# eBox_ACdetect2.net
KiCad netlist of a schematic drawn in Altium Designer
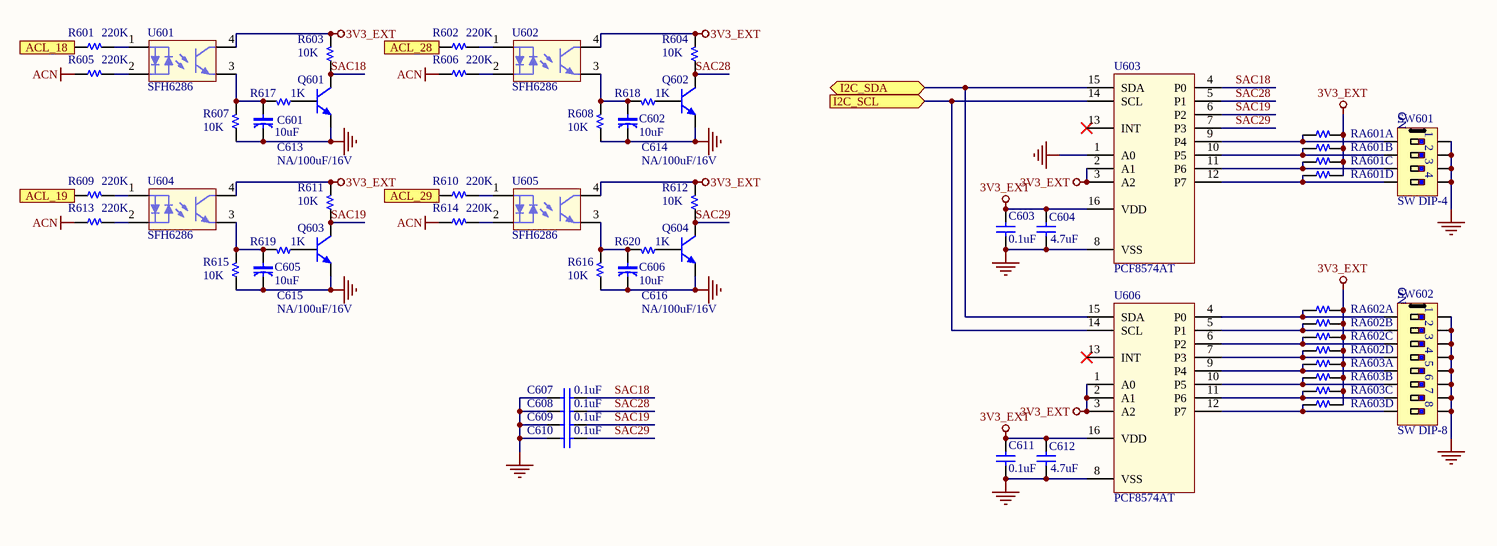
[diagram p0: eBox_ACdetect2.SchDoc]

(export (version "E")
  (design (tool "Eeschema 10.0.6"))
  (components
    (comp (ref "C601")
      (value "10uF")
      (footprint "C 0805")
      (description "CAP CER 0.1UF 50V X7R 0805")
      (libsource (lib "chipfc_altium_libs") (part "Capacitor NP"))
    )
    (comp (ref "C602")
      (value "10uF")
      (footprint "C 0805")
      (description "CAP CER 0.1UF 50V X7R 0805")
      (libsource (lib "chipfc_altium_libs") (part "Capacitor NP"))
    )
    (comp (ref "C603")
      (value "0.1uF")
      (footprint "C 0603")
      (description "CAP CER 0.1UF 50V X7R 0603")
      (libsource (lib "chipfc_altium_libs") (part "Capacitor NP"))
    )
    (comp (ref "C604")
      (value "4.7uF")
      (footprint "C 0603")
      (description "CAP CER 4.7UF 50V X7R 0603")
      (libsource (lib "chipfc_altium_libs") (part "Capacitor NP"))
    )
    (comp (ref "C605")
      (value "10uF")
      (footprint "C 0805")
      (description "CAP CER 0.1UF 50V X7R 0805")
      (libsource (lib "chipfc_altium_libs") (part "Capacitor NP"))
    )
    (comp (ref "C606")
      (value "10uF")
      (footprint "C 0805")
      (description "CAP CER 0.1UF 50V X7R 0805")
      (libsource (lib "chipfc_altium_libs") (part "Capacitor NP"))
    )
    (comp (ref "C607")
      (value "0.1uF")
      (footprint "C 0805")
      (description "CAP CER 0.1UF 50V X7R 0805")
      (libsource (lib "chipfc_altium_libs") (part "Capacitor NP"))
    )
    (comp (ref "C608")
      (value "0.1uF")
      (footprint "C 0805")
      (description "CAP CER 0.1UF 50V X7R 0805")
      (libsource (lib "chipfc_altium_libs") (part "Capacitor NP"))
    )
    (comp (ref "C609")
      (value "0.1uF")
      (footprint "C 0805")
      (description "CAP CER 0.1UF 50V X7R 0805")
      (libsource (lib "chipfc_altium_libs") (part "Capacitor NP"))
    )
    (comp (ref "C610")
      (value "0.1uF")
      (footprint "C 0805")
      (description "CAP CER 0.1UF 50V X7R 0805")
      (libsource (lib "chipfc_altium_libs") (part "Capacitor NP"))
    )
    (comp (ref "C611")
      (value "0.1uF")
      (footprint "C 0603")
      (description "CAP CER 0.1UF 50V X7R 0603")
      (libsource (lib "chipfc_altium_libs") (part "Capacitor NP"))
    )
    (comp (ref "C612")
      (value "4.7uF")
      (footprint "C 0603")
      (description "CAP CER 4.7UF 50V X7R 0603")
      (libsource (lib "chipfc_altium_libs") (part "Capacitor NP"))
    )
    (comp (ref "C613")
      (value "NA/100uF/16V")
      (footprint "CYL/D.200/LS.75")
      (description "CAP ALUM 100UF 20% 16V RADIAL")
      (libsource (lib "chipfc_altium_libs") (part "Capacitor"))
    )
    (comp (ref "C614")
      (value "NA/100uF/16V")
      (footprint "CYL/D.200/LS.75")
      (description "CAP ALUM 100UF 20% 16V RADIAL")
      (libsource (lib "chipfc_altium_libs") (part "Capacitor"))
    )
    (comp (ref "C615")
      (value "NA/100uF/16V")
      (footprint "CYL/D.200/LS.75")
      (description "CAP ALUM 100UF 20% 16V RADIAL")
      (libsource (lib "chipfc_altium_libs") (part "Capacitor"))
    )
    (comp (ref "C616")
      (value "NA/100uF/16V")
      (footprint "CYL/D.200/LS.75")
      (description "CAP ALUM 100UF 20% 16V RADIAL")
      (libsource (lib "chipfc_altium_libs") (part "Capacitor"))
    )
    (comp (ref "Q601")
      (value "MMBT3904LT1G")
      (footprint "SOT-23")
      (description "TRANS NPN 40V 0.2A SOT23")
      (libsource (lib "chipfc_altium_libs") (part "Transistor NPN"))
    )
    (comp (ref "Q602")
      (value "MMBT3904LT1G")
      (footprint "SOT-23")
      (description "TRANS NPN 40V 0.2A SOT23")
      (libsource (lib "chipfc_altium_libs") (part "Transistor NPN"))
    )
    (comp (ref "Q603")
      (value "MMBT3904LT1G")
      (footprint "SOT-23")
      (description "TRANS NPN 40V 0.2A SOT23")
      (libsource (lib "chipfc_altium_libs") (part "Transistor NPN"))
    )
    (comp (ref "Q604")
      (value "MMBT3904LT1G")
      (footprint "SOT-23")
      (description "TRANS NPN 40V 0.2A SOT23")
      (libsource (lib "chipfc_altium_libs") (part "Transistor NPN"))
    )
    (comp (ref "R601")
      (value "220K")
      (footprint "R 0805")
      (description "RES SMD 220K OHM 1% 1/8W 0805")
      (libsource (lib "chipfc_altium_libs") (part "Resistor"))
    )
    (comp (ref "R602")
      (value "220K")
      (footprint "R 0805")
      (description "RES SMD 220K OHM 1% 1/8W 0805")
      (libsource (lib "chipfc_altium_libs") (part "Resistor"))
    )
    (comp (ref "R603")
      (value "10K")
      (footprint "R 0805")
      (description "RES SMD 10K OHM 1% 1/8W 0805")
      (libsource (lib "chipfc_altium_libs") (part "Resistor"))
    )
    (comp (ref "R604")
      (value "10K")
      (footprint "R 0805")
      (description "RES SMD 10K OHM 1% 1/8W 0805")
      (libsource (lib "chipfc_altium_libs") (part "Resistor"))
    )
    (comp (ref "R605")
      (value "220K")
      (footprint "R 0805")
      (description "RES SMD 220K OHM 1% 1/8W 0805")
      (libsource (lib "chipfc_altium_libs") (part "Resistor"))
    )
    (comp (ref "R606")
      (value "220K")
      (footprint "R 0805")
      (description "RES SMD 220K OHM 1% 1/8W 0805")
      (libsource (lib "chipfc_altium_libs") (part "Resistor"))
    )
    (comp (ref "R607")
      (value "10K")
      (footprint "R 0805")
      (description "RES SMD 10K OHM 1% 1/8W 0805")
      (libsource (lib "chipfc_altium_libs") (part "Resistor"))
    )
    (comp (ref "R608")
      (value "10K")
      (footprint "R 0805")
      (description "RES SMD 10K OHM 1% 1/8W 0805")
      (libsource (lib "chipfc_altium_libs") (part "Resistor"))
    )
    (comp (ref "R609")
      (value "220K")
      (footprint "R 0805")
      (description "RES SMD 220K OHM 1% 1/8W 0805")
      (libsource (lib "chipfc_altium_libs") (part "Resistor"))
    )
    (comp (ref "R610")
      (value "220K")
      (footprint "R 0805")
      (description "RES SMD 220K OHM 1% 1/8W 0805")
      (libsource (lib "chipfc_altium_libs") (part "Resistor"))
    )
    (comp (ref "R611")
      (value "10K")
      (footprint "R 0805")
      (description "RES SMD 10K OHM 1% 1/8W 0805")
      (libsource (lib "chipfc_altium_libs") (part "Resistor"))
    )
    (comp (ref "R612")
      (value "10K")
      (footprint "R 0805")
      (description "RES SMD 10K OHM 1% 1/8W 0805")
      (libsource (lib "chipfc_altium_libs") (part "Resistor"))
    )
    (comp (ref "R613")
      (value "220K")
      (footprint "R 0805")
      (description "RES SMD 220K OHM 1% 1/8W 0805")
      (libsource (lib "chipfc_altium_libs") (part "Resistor"))
    )
    (comp (ref "R614")
      (value "220K")
      (footprint "R 0805")
      (description "RES SMD 220K OHM 1% 1/8W 0805")
      (libsource (lib "chipfc_altium_libs") (part "Resistor"))
    )
    (comp (ref "R615")
      (value "10K")
      (footprint "R 0805")
      (description "RES SMD 10K OHM 1% 1/8W 0805")
      (libsource (lib "chipfc_altium_libs") (part "Resistor"))
    )
    (comp (ref "R616")
      (value "10K")
      (footprint "R 0805")
      (description "RES SMD 10K OHM 1% 1/8W 0805")
      (libsource (lib "chipfc_altium_libs") (part "Resistor"))
    )
    (comp (ref "R617")
      (value "1K")
      (footprint "R 0805")
      (description "RES SMD 1K OHM 5% 1/8W 0805")
      (libsource (lib "chipfc_altium_libs") (part "Resistor"))
    )
    (comp (ref "R618")
      (value "1K")
      (footprint "R 0805")
      (description "RES SMD 1K OHM 5% 1/8W 0805")
      (libsource (lib "chipfc_altium_libs") (part "Resistor"))
    )
    (comp (ref "R619")
      (value "1K")
      (footprint "R 0805")
      (description "RES SMD 1K OHM 5% 1/8W 0805")
      (libsource (lib "chipfc_altium_libs") (part "Resistor"))
    )
    (comp (ref "R620")
      (value "1K")
      (footprint "R 0805")
      (description "RES SMD 1K OHM 5% 1/8W 0805")
      (libsource (lib "chipfc_altium_libs") (part "Resistor"))
    )
    (comp (ref "RA601")
      (value "10K")
      (footprint "RAx4 1206 (3216)")
      (description "10K 1/10W 5% Chip Resistor Array (SMD0603x4)")
      (libsource (lib "chipfc_altium_libs") (part "Resistor Array x4"))
    )
    (comp (ref "RA602")
      (value "10K")
      (footprint "RAx4 1206 (3216)")
      (description "10K 1/10W 5% Chip Resistor Array (SMD0603x4)")
      (libsource (lib "chipfc_altium_libs") (part "Resistor Array x4"))
    )
    (comp (ref "RA603")
      (value "10K")
      (footprint "RAx4 1206 (3216)")
      (description "10K 1/10W 5% Chip Resistor Array (SMD0603x4)")
      (libsource (lib "chipfc_altium_libs") (part "Resistor Array x4"))
    )
    (comp (ref "SW601")
      (value "SW DIP-4")
      (footprint "SW/DIP4")
      (libsource (lib "chipfc_altium_libs") (part "SW DIP-4"))
    )
    (comp (ref "SW602")
      (value "SW DIP-8")
      (footprint "SW/DIP8/300")
      (libsource (lib "chipfc_altium_libs") (part "SW DIP-8"))
    )
    (comp (ref "U601")
      (value "SFH6286")
      (footprint "SOP4 - SFH6286")
      (libsource (lib "chipfc_altium_libs") (part "SFH6286"))
    )
    (comp (ref "U602")
      (value "SFH6286")
      (footprint "SOP4 - SFH6286")
      (libsource (lib "chipfc_altium_libs") (part "SFH6286"))
    )
    (comp (ref "U603")
      (value "PCF8574AT")
      (footprint "SO16/PCF8574AT")
      (description "Remote 8-bit I/O expander for I2C-bus with interrupt")
      (fields (field (name "PART NO") "PCF8574AT/3"))
      (libsource (lib "chipfc_altium_libs") (part "PCF8574AT"))
    )
    (comp (ref "U604")
      (value "SFH6286")
      (footprint "SOP4 - SFH6286")
      (libsource (lib "chipfc_altium_libs") (part "SFH6286"))
    )
    (comp (ref "U605")
      (value "SFH6286")
      (footprint "SOP4 - SFH6286")
      (libsource (lib "chipfc_altium_libs") (part "SFH6286"))
    )
    (comp (ref "U606")
      (value "PCF8574AT")
      (footprint "SO16/PCF8574AT")
      (description "Remote 8-bit I/O expander for I2C-bus with interrupt")
      (fields (field (name "PART NO") "PCF8574AT/3"))
      (libsource (lib "chipfc_altium_libs") (part "PCF8574AT"))
    )
  )
  (nets
    (net (code "1") (name "/ACL_18") (class "Default")
      (node (ref "R601") (pin "1") (pinfunction "1_1") (pintype "passive"))
    )
    (net (code "2") (name "/ACL_19") (class "Default")
      (node (ref "R609") (pin "1") (pinfunction "1_1") (pintype "passive"))
    )
    (net (code "3") (name "/ACL_28") (class "Default")
      (node (ref "R602") (pin "1") (pinfunction "1_1") (pintype "passive"))
    )
    (net (code "4") (name "/ACL_29") (class "Default")
      (node (ref "R610") (pin "1") (pinfunction "1_1") (pintype "passive"))
    )
    (net (code "5") (name "/I2C_SCL") (class "Default")
      (node (ref "U603") (pin "14") (pinfunction "SCL_14") (pintype "passive"))
      (node (ref "U606") (pin "14") (pinfunction "SCL_14") (pintype "passive"))
    )
    (net (code "6") (name "/I2C_SDA") (class "Default")
      (node (ref "U603") (pin "15") (pinfunction "SDA_15") (pintype "passive"))
      (node (ref "U606") (pin "15") (pinfunction "SDA_15") (pintype "passive"))
    )
    (net (code "7") (name "/SAC18") (class "Default")
      (node (ref "C607") (pin "2") (pinfunction "2_2") (pintype "passive"))
      (node (ref "Q601") (pin "3") (pinfunction "C_3") (pintype "passive"))
      (node (ref "R603") (pin "1") (pinfunction "1_1") (pintype "passive"))
      (node (ref "U603") (pin "4") (pinfunction "P0_4") (pintype "passive"))
    )
    (net (code "8") (name "/SAC19") (class "Default")
      (node (ref "C609") (pin "2") (pinfunction "2_2") (pintype "passive"))
      (node (ref "Q603") (pin "3") (pinfunction "C_3") (pintype "passive"))
      (node (ref "R611") (pin "1") (pinfunction "1_1") (pintype "passive"))
      (node (ref "U603") (pin "6") (pinfunction "P2_6") (pintype "passive"))
    )
    (net (code "9") (name "/SAC28") (class "Default")
      (node (ref "C608") (pin "2") (pinfunction "2_2") (pintype "passive"))
      (node (ref "Q602") (pin "3") (pinfunction "C_3") (pintype "passive"))
      (node (ref "R604") (pin "1") (pinfunction "1_1") (pintype "passive"))
      (node (ref "U603") (pin "5") (pinfunction "P1_5") (pintype "passive"))
    )
    (net (code "10") (name "/SAC29") (class "Default")
      (node (ref "C610") (pin "2") (pinfunction "2_2") (pintype "passive"))
      (node (ref "Q604") (pin "3") (pinfunction "C_3") (pintype "passive"))
      (node (ref "R612") (pin "1") (pinfunction "1_1") (pintype "passive"))
      (node (ref "U603") (pin "7") (pinfunction "P3_7") (pintype "passive"))
    )
    (net (code "11") (name "3V3_EXT") (class "Default")
      (node (ref "C603") (pin "1") (pinfunction "1_1") (pintype "passive"))
      (node (ref "C604") (pin "1") (pinfunction "1_1") (pintype "passive"))
      (node (ref "C611") (pin "1") (pinfunction "1_1") (pintype "passive"))
      (node (ref "C612") (pin "1") (pinfunction "1_1") (pintype "passive"))
      (node (ref "R603") (pin "2") (pinfunction "2_2") (pintype "passive"))
      (node (ref "R604") (pin "2") (pinfunction "2_2") (pintype "passive"))
      (node (ref "R611") (pin "2") (pinfunction "2_2") (pintype "passive"))
      (node (ref "R612") (pin "2") (pinfunction "2_2") (pintype "passive"))
      (node (ref "RA601") (pin "5") (pinfunction "5_5") (pintype "passive"))
      (node (ref "RA601") (pin "6") (pinfunction "6_6") (pintype "passive"))
      (node (ref "RA601") (pin "7") (pinfunction "7_7") (pintype "passive"))
      (node (ref "RA601") (pin "8") (pinfunction "8_8") (pintype "passive"))
      (node (ref "RA602") (pin "5") (pinfunction "5_5") (pintype "passive"))
      (node (ref "RA602") (pin "6") (pinfunction "6_6") (pintype "passive"))
      (node (ref "RA602") (pin "7") (pinfunction "7_7") (pintype "passive"))
      (node (ref "RA602") (pin "8") (pinfunction "8_8") (pintype "passive"))
      (node (ref "RA603") (pin "5") (pinfunction "5_5") (pintype "passive"))
      (node (ref "RA603") (pin "6") (pinfunction "6_6") (pintype "passive"))
      (node (ref "RA603") (pin "7") (pinfunction "7_7") (pintype "passive"))
      (node (ref "RA603") (pin "8") (pinfunction "8_8") (pintype "passive"))
      (node (ref "U601") (pin "4") (pinfunction "C_4") (pintype "passive"))
      (node (ref "U602") (pin "4") (pinfunction "C_4") (pintype "passive"))
      (node (ref "U603") (pin "16") (pinfunction "VDD_16") (pintype "passive"))
      (node (ref "U603") (pin "2") (pinfunction "A1_2") (pintype "passive"))
      (node (ref "U603") (pin "3") (pinfunction "A2_3") (pintype "passive"))
      (node (ref "U604") (pin "4") (pinfunction "C_4") (pintype "passive"))
      (node (ref "U605") (pin "4") (pinfunction "C_4") (pintype "passive"))
      (node (ref "U606") (pin "1") (pinfunction "A0_1") (pintype "passive"))
      (node (ref "U606") (pin "16") (pinfunction "VDD_16") (pintype "passive"))
      (node (ref "U606") (pin "2") (pinfunction "A1_2") (pintype "passive"))
      (node (ref "U606") (pin "3") (pinfunction "A2_3") (pintype "passive"))
    )
    (net (code "12") (name "ACN") (class "Default")
      (node (ref "R605") (pin "1") (pinfunction "1_1") (pintype "passive"))
      (node (ref "R606") (pin "1") (pinfunction "1_1") (pintype "passive"))
      (node (ref "R613") (pin "1") (pinfunction "1_1") (pintype "passive"))
      (node (ref "R614") (pin "1") (pinfunction "1_1") (pintype "passive"))
    )
    (net (code "13") (name "GND") (class "Default")
      (node (ref "C601") (pin "2") (pinfunction "2_2") (pintype "passive"))
      (node (ref "C602") (pin "2") (pinfunction "2_2") (pintype "passive"))
      (node (ref "C603") (pin "2") (pinfunction "2_2") (pintype "passive"))
      (node (ref "C604") (pin "2") (pinfunction "2_2") (pintype "passive"))
      (node (ref "C605") (pin "2") (pinfunction "2_2") (pintype "passive"))
      (node (ref "C606") (pin "2") (pinfunction "2_2") (pintype "passive"))
      (node (ref "C607") (pin "1") (pinfunction "1_1") (pintype "passive"))
      (node (ref "C608") (pin "1") (pinfunction "1_1") (pintype "passive"))
      (node (ref "C609") (pin "1") (pinfunction "1_1") (pintype "passive"))
      (node (ref "C610") (pin "1") (pinfunction "1_1") (pintype "passive"))
      (node (ref "C611") (pin "2") (pinfunction "2_2") (pintype "passive"))
      (node (ref "C612") (pin "2") (pinfunction "2_2") (pintype "passive"))
      (node (ref "C613") (pin "2") (pinfunction "2_2") (pintype "passive"))
      (node (ref "C614") (pin "2") (pinfunction "2_2") (pintype "passive"))
      (node (ref "C615") (pin "2") (pinfunction "2_2") (pintype "passive"))
      (node (ref "C616") (pin "2") (pinfunction "2_2") (pintype "passive"))
      (node (ref "Q601") (pin "2") (pinfunction "E_2") (pintype "passive"))
      (node (ref "Q602") (pin "2") (pinfunction "E_2") (pintype "passive"))
      (node (ref "Q603") (pin "2") (pinfunction "E_2") (pintype "passive"))
      (node (ref "Q604") (pin "2") (pinfunction "E_2") (pintype "passive"))
      (node (ref "R607") (pin "1") (pinfunction "1_1") (pintype "passive"))
      (node (ref "R608") (pin "1") (pinfunction "1_1") (pintype "passive"))
      (node (ref "R615") (pin "1") (pinfunction "1_1") (pintype "passive"))
      (node (ref "R616") (pin "1") (pinfunction "1_1") (pintype "passive"))
      (node (ref "SW601") (pin "1") (pinfunction "1_1") (pintype "passive"))
      (node (ref "SW601") (pin "2") (pinfunction "2_2") (pintype "passive"))
      (node (ref "SW601") (pin "3") (pinfunction "3_3") (pintype "passive"))
      (node (ref "SW601") (pin "4") (pinfunction "4_4") (pintype "passive"))
      (node (ref "SW602") (pin "1") (pinfunction "1_1") (pintype "passive"))
      (node (ref "SW602") (pin "2") (pinfunction "2_2") (pintype "passive"))
      (node (ref "SW602") (pin "3") (pinfunction "3_3") (pintype "passive"))
      (node (ref "SW602") (pin "4") (pinfunction "4_4") (pintype "passive"))
      (node (ref "SW602") (pin "5") (pinfunction "5_5") (pintype "passive"))
      (node (ref "SW602") (pin "6") (pinfunction "6_6") (pintype "passive"))
      (node (ref "SW602") (pin "7") (pinfunction "7_7") (pintype "passive"))
      (node (ref "SW602") (pin "8") (pinfunction "8_8") (pintype "passive"))
      (node (ref "U603") (pin "1") (pinfunction "A0_1") (pintype "passive"))
      (node (ref "U603") (pin "8") (pinfunction "VSS_8") (pintype "passive"))
      (node (ref "U606") (pin "8") (pinfunction "VSS_8") (pintype "passive"))
    )
    (net (code "14") (name "Net-(Q601-B)") (class "Default")
      (node (ref "Q601") (pin "1") (pinfunction "B_1") (pintype "passive"))
      (node (ref "R617") (pin "1") (pinfunction "1_1") (pintype "passive"))
    )
    (net (code "15") (name "Net-(Q602-B)") (class "Default")
      (node (ref "Q602") (pin "1") (pinfunction "B_1") (pintype "passive"))
      (node (ref "R618") (pin "1") (pinfunction "1_1") (pintype "passive"))
    )
    (net (code "16") (name "Net-(Q603-B)") (class "Default")
      (node (ref "Q603") (pin "1") (pinfunction "B_1") (pintype "passive"))
      (node (ref "R619") (pin "1") (pinfunction "1_1") (pintype "passive"))
    )
    (net (code "17") (name "Net-(Q604-B)") (class "Default")
      (node (ref "Q604") (pin "1") (pinfunction "B_1") (pintype "passive"))
      (node (ref "R620") (pin "1") (pinfunction "1_1") (pintype "passive"))
    )
    (net (code "18") (name "Net-(U601-A{slash}C)") (class "Default")
      (node (ref "R601") (pin "2") (pinfunction "2_2") (pintype "passive"))
      (node (ref "U601") (pin "1") (pinfunction "A/C_1") (pintype "passive"))
    )
    (net (code "19") (name "Net-(U601-C{slash}A)") (class "Default")
      (node (ref "R605") (pin "2") (pinfunction "2_2") (pintype "passive"))
      (node (ref "U601") (pin "2") (pinfunction "C/A_2") (pintype "passive"))
    )
    (net (code "20") (name "Net-(U601-E)") (class "Default")
      (node (ref "C601") (pin "1") (pinfunction "1_1") (pintype "passive"))
      (node (ref "C613") (pin "1") (pinfunction "1_1") (pintype "passive"))
      (node (ref "R607") (pin "2") (pinfunction "2_2") (pintype "passive"))
      (node (ref "R617") (pin "2") (pinfunction "2_2") (pintype "passive"))
      (node (ref "U601") (pin "3") (pinfunction "E_3") (pintype "passive"))
    )
    (net (code "21") (name "Net-(U602-A{slash}C)") (class "Default")
      (node (ref "R602") (pin "2") (pinfunction "2_2") (pintype "passive"))
      (node (ref "U602") (pin "1") (pinfunction "A/C_1") (pintype "passive"))
    )
    (net (code "22") (name "Net-(U602-C{slash}A)") (class "Default")
      (node (ref "R606") (pin "2") (pinfunction "2_2") (pintype "passive"))
      (node (ref "U602") (pin "2") (pinfunction "C/A_2") (pintype "passive"))
    )
    (net (code "23") (name "Net-(U602-E)") (class "Default")
      (node (ref "C602") (pin "1") (pinfunction "1_1") (pintype "passive"))
      (node (ref "C614") (pin "1") (pinfunction "1_1") (pintype "passive"))
      (node (ref "R608") (pin "2") (pinfunction "2_2") (pintype "passive"))
      (node (ref "R618") (pin "2") (pinfunction "2_2") (pintype "passive"))
      (node (ref "U602") (pin "3") (pinfunction "E_3") (pintype "passive"))
    )
    (net (code "24") (name "Net-(U603-P4)") (class "Default")
      (node (ref "RA601") (pin "1") (pinfunction "1_1") (pintype "passive"))
      (node (ref "SW601") (pin "8") (pinfunction "8_8") (pintype "passive"))
      (node (ref "U603") (pin "9") (pinfunction "P4_9") (pintype "passive"))
    )
    (net (code "25") (name "Net-(U603-P5)") (class "Default")
      (node (ref "RA601") (pin "2") (pinfunction "2_2") (pintype "passive"))
      (node (ref "SW601") (pin "7") (pinfunction "7_7") (pintype "passive"))
      (node (ref "U603") (pin "10") (pinfunction "P5_10") (pintype "passive"))
    )
    (net (code "26") (name "Net-(U603-P6)") (class "Default")
      (node (ref "RA601") (pin "3") (pinfunction "3_3") (pintype "passive"))
      (node (ref "SW601") (pin "6") (pinfunction "6_6") (pintype "passive"))
      (node (ref "U603") (pin "11") (pinfunction "P6_11") (pintype "passive"))
    )
    (net (code "27") (name "Net-(U603-P7)") (class "Default")
      (node (ref "RA601") (pin "4") (pinfunction "4_4") (pintype "passive"))
      (node (ref "SW601") (pin "5") (pinfunction "5_5") (pintype "passive"))
      (node (ref "U603") (pin "12") (pinfunction "P7_12") (pintype "passive"))
    )
    (net (code "28") (name "Net-(U604-A{slash}C)") (class "Default")
      (node (ref "R609") (pin "2") (pinfunction "2_2") (pintype "passive"))
      (node (ref "U604") (pin "1") (pinfunction "A/C_1") (pintype "passive"))
    )
    (net (code "29") (name "Net-(U604-C{slash}A)") (class "Default")
      (node (ref "R613") (pin "2") (pinfunction "2_2") (pintype "passive"))
      (node (ref "U604") (pin "2") (pinfunction "C/A_2") (pintype "passive"))
    )
    (net (code "30") (name "Net-(U604-E)") (class "Default")
      (node (ref "C605") (pin "1") (pinfunction "1_1") (pintype "passive"))
      (node (ref "C615") (pin "1") (pinfunction "1_1") (pintype "passive"))
      (node (ref "R615") (pin "2") (pinfunction "2_2") (pintype "passive"))
      (node (ref "R619") (pin "2") (pinfunction "2_2") (pintype "passive"))
      (node (ref "U604") (pin "3") (pinfunction "E_3") (pintype "passive"))
    )
    (net (code "31") (name "Net-(U605-A{slash}C)") (class "Default")
      (node (ref "R610") (pin "2") (pinfunction "2_2") (pintype "passive"))
      (node (ref "U605") (pin "1") (pinfunction "A/C_1") (pintype "passive"))
    )
    (net (code "32") (name "Net-(U605-C{slash}A)") (class "Default")
      (node (ref "R614") (pin "2") (pinfunction "2_2") (pintype "passive"))
      (node (ref "U605") (pin "2") (pinfunction "C/A_2") (pintype "passive"))
    )
    (net (code "33") (name "Net-(U605-E)") (class "Default")
      (node (ref "C606") (pin "1") (pinfunction "1_1") (pintype "passive"))
      (node (ref "C616") (pin "1") (pinfunction "1_1") (pintype "passive"))
      (node (ref "R616") (pin "2") (pinfunction "2_2") (pintype "passive"))
      (node (ref "R620") (pin "2") (pinfunction "2_2") (pintype "passive"))
      (node (ref "U605") (pin "3") (pinfunction "E_3") (pintype "passive"))
    )
    (net (code "34") (name "Net-(U606-P0)") (class "Default")
      (node (ref "RA602") (pin "1") (pinfunction "1_1") (pintype "passive"))
      (node (ref "SW602") (pin "16") (pinfunction "16_16") (pintype "passive"))
      (node (ref "U606") (pin "4") (pinfunction "P0_4") (pintype "passive"))
    )
    (net (code "35") (name "Net-(U606-P1)") (class "Default")
      (node (ref "RA602") (pin "2") (pinfunction "2_2") (pintype "passive"))
      (node (ref "SW602") (pin "15") (pinfunction "15_15") (pintype "passive"))
      (node (ref "U606") (pin "5") (pinfunction "P1_5") (pintype "passive"))
    )
    (net (code "36") (name "Net-(U606-P2)") (class "Default")
      (node (ref "RA602") (pin "3") (pinfunction "3_3") (pintype "passive"))
      (node (ref "SW602") (pin "14") (pinfunction "14_14") (pintype "passive"))
      (node (ref "U606") (pin "6") (pinfunction "P2_6") (pintype "passive"))
    )
    (net (code "37") (name "Net-(U606-P3)") (class "Default")
      (node (ref "RA602") (pin "4") (pinfunction "4_4") (pintype "passive"))
      (node (ref "SW602") (pin "13") (pinfunction "13_13") (pintype "passive"))
      (node (ref "U606") (pin "7") (pinfunction "P3_7") (pintype "passive"))
    )
    (net (code "38") (name "Net-(U606-P4)") (class "Default")
      (node (ref "RA603") (pin "1") (pinfunction "1_1") (pintype "passive"))
      (node (ref "SW602") (pin "12") (pinfunction "12_12") (pintype "passive"))
      (node (ref "U606") (pin "9") (pinfunction "P4_9") (pintype "passive"))
    )
    (net (code "39") (name "Net-(U606-P5)") (class "Default")
      (node (ref "RA603") (pin "2") (pinfunction "2_2") (pintype "passive"))
      (node (ref "SW602") (pin "11") (pinfunction "11_11") (pintype "passive"))
      (node (ref "U606") (pin "10") (pinfunction "P5_10") (pintype "passive"))
    )
    (net (code "40") (name "Net-(U606-P6)") (class "Default")
      (node (ref "RA603") (pin "3") (pinfunction "3_3") (pintype "passive"))
      (node (ref "SW602") (pin "10") (pinfunction "10_10") (pintype "passive"))
      (node (ref "U606") (pin "11") (pinfunction "P6_11") (pintype "passive"))
    )
    (net (code "41") (name "Net-(U606-P7)") (class "Default")
      (node (ref "RA603") (pin "4") (pinfunction "4_4") (pintype "passive"))
      (node (ref "SW602") (pin "9") (pinfunction "9_9") (pintype "passive"))
      (node (ref "U606") (pin "12") (pinfunction "P7_12") (pintype "passive"))
    )
    (net (code "42") (name "unconnected-(U603-INT-Pad13)") (class "Default")
      (node (ref "U603") (pin "13") (pinfunction "INT_13") (pintype "passive+no_connect"))
    )
    (net (code "43") (name "unconnected-(U606-INT-Pad13)") (class "Default")
      (node (ref "U606") (pin "13") (pinfunction "INT_13") (pintype "passive+no_connect"))
    )
  )
)
